# STC8G1K08A.net
KiCad netlist of a schematic drawn in EasyEDA Pro
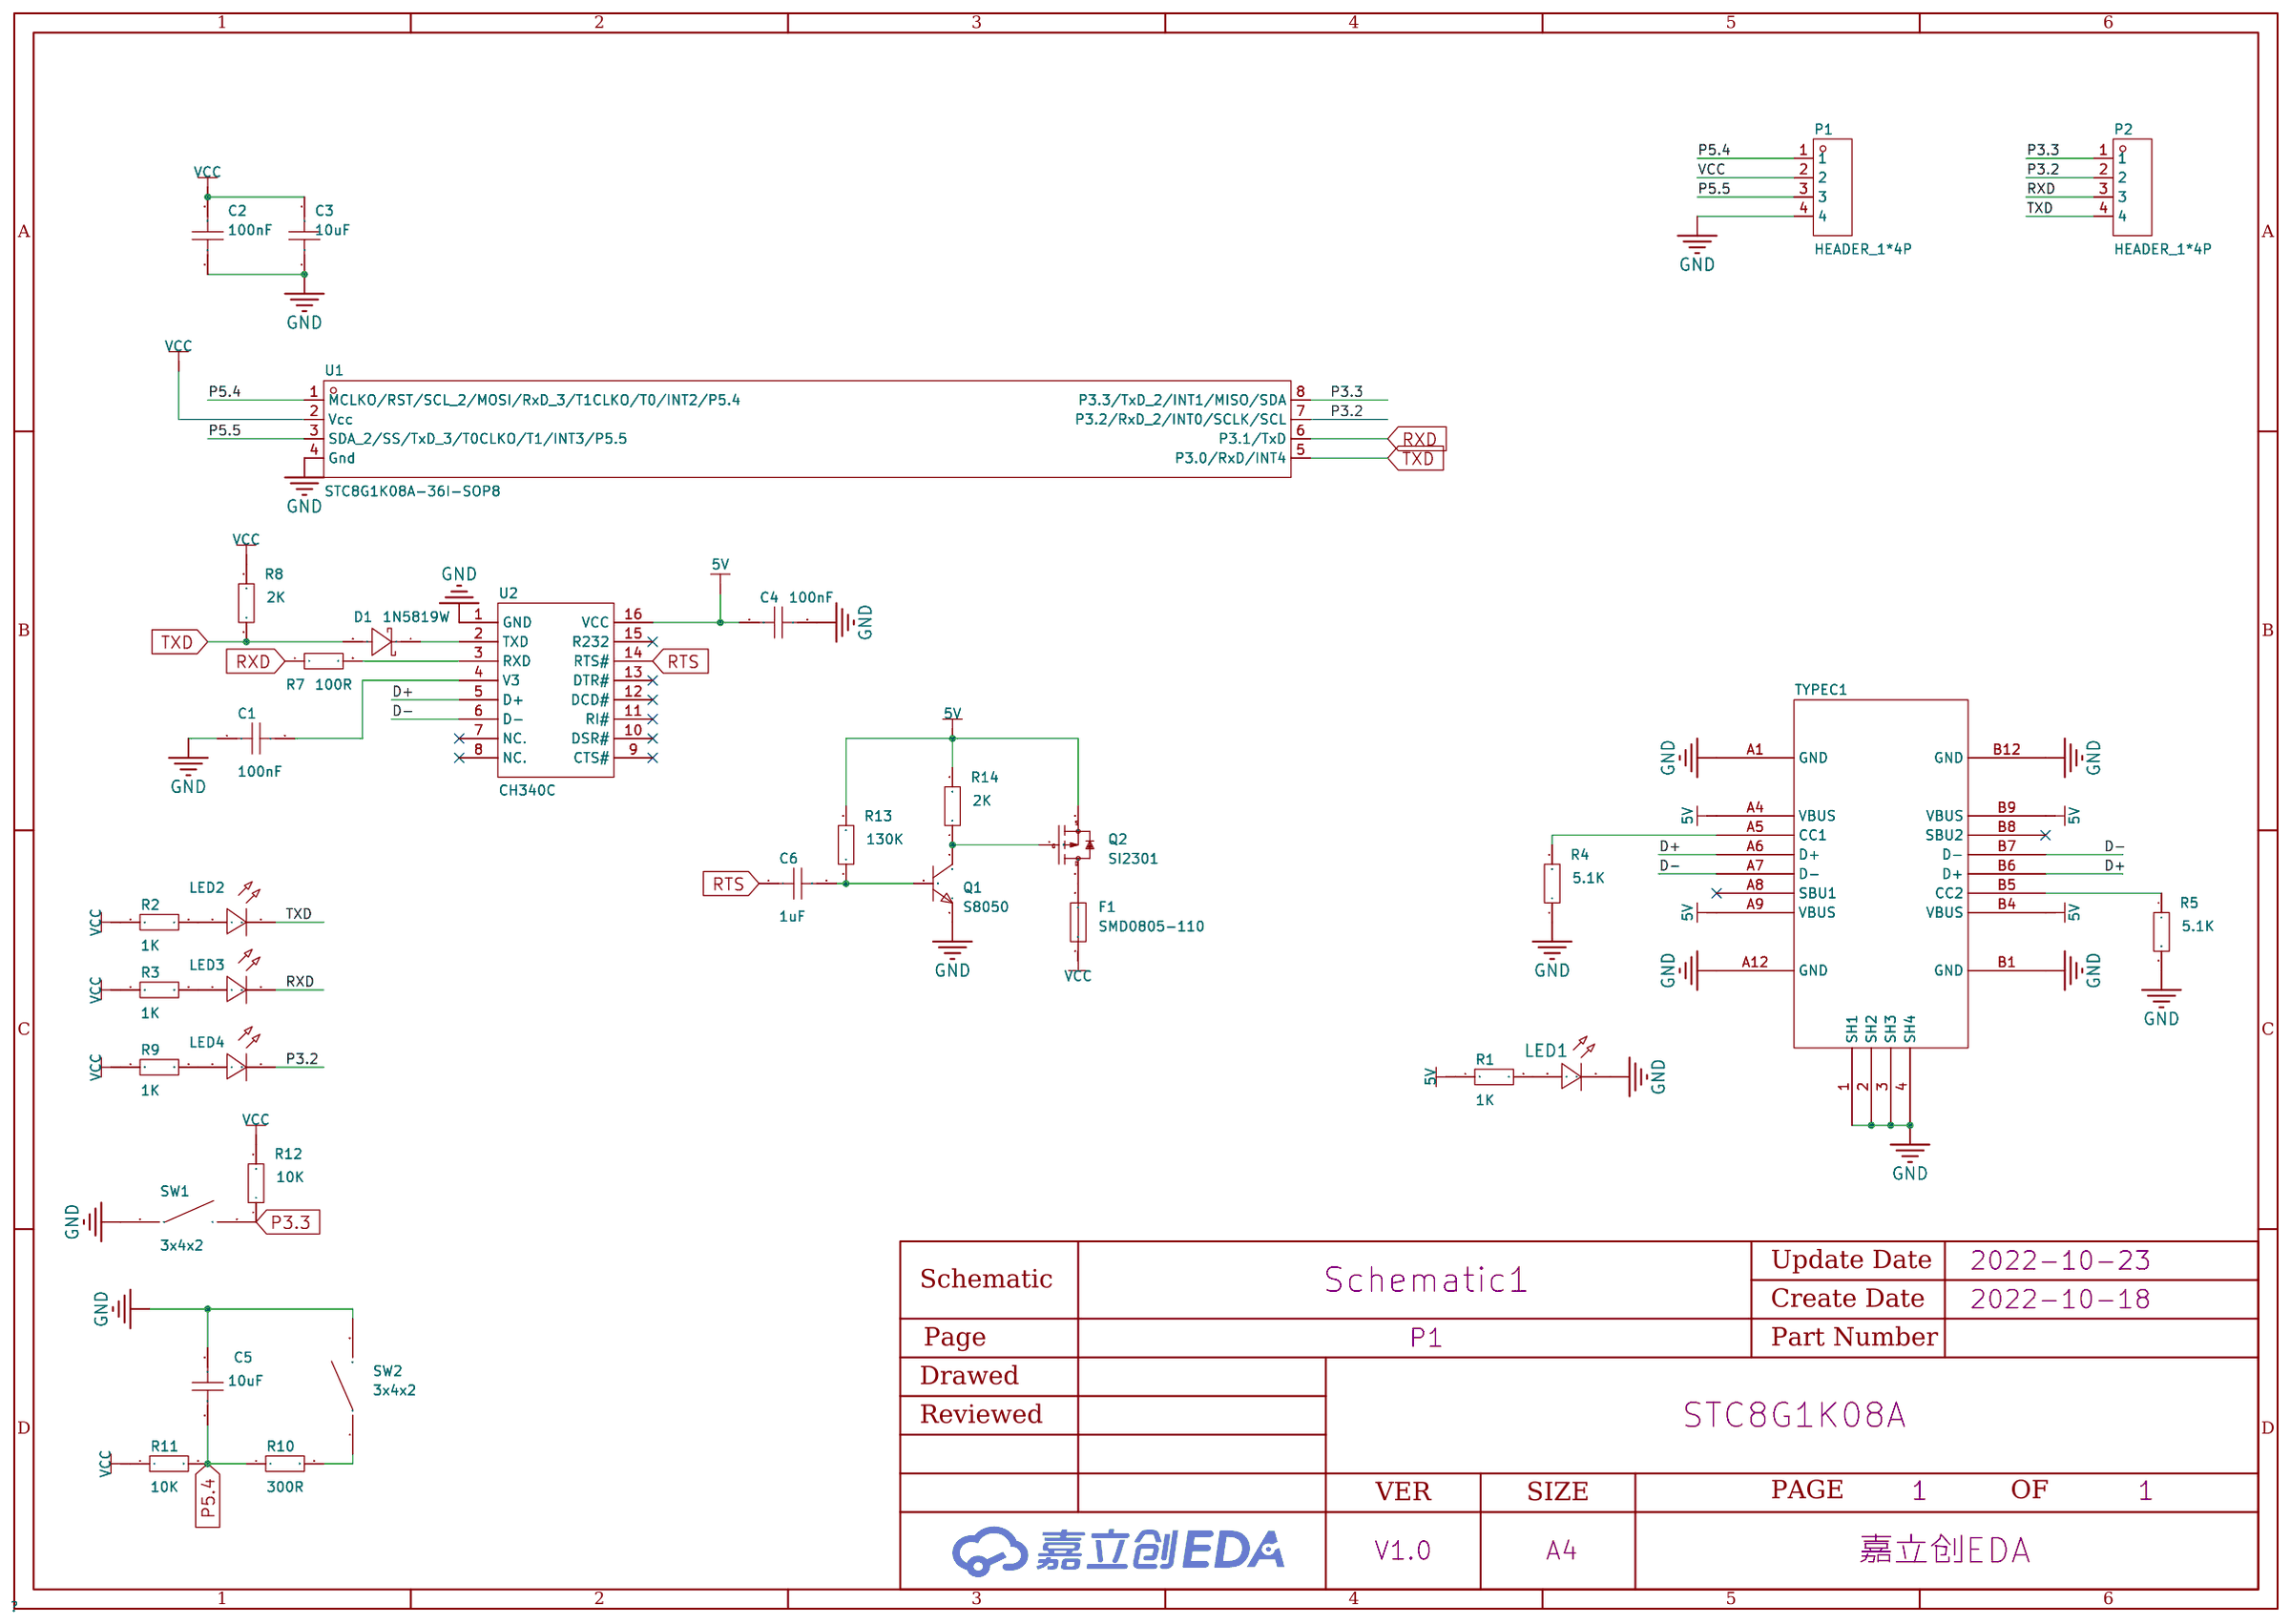
[diagram p0: schematic sheet]

(export (version "E")
  (design (tool "Eeschema 10.0.6"))
  (components
    (comp (ref "C1")
      (value "100nF")
      (footprint "easyedapro:C0603")
      (libsource (lib "easyedapro") (part "C1210X7R475K630NT"))
    )
    (comp (ref "C2")
      (value "100nF")
      (footprint "easyedapro:C0603")
      (libsource (lib "easyedapro") (part "C1210X7R475K630NT"))
    )
    (comp (ref "C3")
      (value "100nF")
      (footprint "easyedapro:C0603")
      (libsource (lib "easyedapro") (part "C1210X7R475K630NT"))
    )
    (comp (ref "C4")
      (value "100nF")
      (footprint "easyedapro:C0603")
      (libsource (lib "easyedapro") (part "C1210X7R475K630NT"))
    )
    (comp (ref "C5")
      (value "100nF")
      (footprint "easyedapro:C0603")
      (libsource (lib "easyedapro") (part "C1210X7R475K630NT"))
    )
    (comp (ref "C6")
      (value "100nF")
      (footprint "easyedapro:C0603")
      (libsource (lib "easyedapro") (part "C1210X7R475K630NT"))
    )
    (comp (ref "D1")
      (value "1N5819W")
      (footprint "easyedapro:SOD-323_L1.7-W1.3-LS2.6-RD-1")
      (description "二极管配置:-;直流反向耐压(Vr):40V;平均整流电流(Io):350mA;正向压降(Vf):600mV@200mA;反向电流(Ir):5A@30V;")
      (fields (field (name "Manufacturer Part") "1N5819WS S4") (field (name "Manufacturer") "KUU"))
      (libsource (lib "easyedapro") (part "1N5819WS S4_C2939001"))
    )
    (comp (ref "F1")
      (value "SMD0805-110")
      (footprint "easyedapro:F0805")
      (fields (field (name "Manufacturer") "DOWO(东沃)"))
      (libsource (lib "easyedapro") (part "SMD0805-110_C883453"))
    )
    (comp (ref "LED1")
      (value "~")
      (footprint "easyedapro:LED0805-RD_RED")
      (libsource (lib "easyedapro") (part "LED_R"))
    )
    (comp (ref "LED2")
      (value "~")
      (footprint "easyedapro:LED0805-RD_RED")
      (libsource (lib "easyedapro") (part "LED_G"))
    )
    (comp (ref "LED3")
      (value "~")
      (footprint "easyedapro:LED0805-RD_RED")
      (libsource (lib "easyedapro") (part "LED_B"))
    )
    (comp (ref "LED4")
      (value "~")
      (footprint "easyedapro:LED0805-RD_RED")
      (libsource (lib "easyedapro") (part "LED_B"))
    )
    (comp (ref "P1")
      (value "HEADER_1*4P")
      (footprint "easyedapro:HDR-TH_4P-P2.54-V-M-1")
      (libsource (lib "easyedapro") (part "HEADER_1*4P"))
    )
    (comp (ref "P2")
      (value "HEADER_1*4P")
      (footprint "easyedapro:HDR-TH_4P-P2.54-V-M-1")
      (libsource (lib "easyedapro") (part "HEADER_1*4P"))
    )
    (comp (ref "Q1")
      (value "S8050")
      (footprint "easyedapro:SOT-23-3_L2.9-W1.3-P1.90-LS2.4-BR")
      (description "NPN 25V 500mA 120-400 SOT-23")
      (fields (field (name "Manufacturer") "Doeshare(德芯)"))
      (libsource (lib "easyedapro") (part "S8050_C2931719"))
    )
    (comp (ref "Q2")
      (value "SI2301")
      (footprint "easyedapro:SOT-23-3_L2.9-W1.6-P1.90-LS2.8-BR")
      (fields (field (name "Manufacturer") "KUU"))
      (libsource (lib "easyedapro") (part "SI2301_C2985938"))
    )
    (comp (ref "R1") (value "10K") (footprint "easyedapro:R0603") (libsource (lib "easyedapro") (part "电阻")))
    (comp (ref "R2") (value "10K") (footprint "easyedapro:R0603") (libsource (lib "easyedapro") (part "电阻")))
    (comp (ref "R3") (value "10K") (footprint "easyedapro:R0603") (libsource (lib "easyedapro") (part "电阻")))
    (comp (ref "R4") (value "10K") (footprint "easyedapro:R0603") (libsource (lib "easyedapro") (part "电阻")))
    (comp (ref "R5") (value "10K") (footprint "easyedapro:R0603") (libsource (lib "easyedapro") (part "电阻")))
    (comp (ref "R7") (value "10K") (footprint "easyedapro:R0603") (libsource (lib "easyedapro") (part "电阻")))
    (comp (ref "R8") (value "10K") (footprint "easyedapro:R0603") (libsource (lib "easyedapro") (part "电阻")))
    (comp (ref "R9") (value "10K") (footprint "easyedapro:R0603") (libsource (lib "easyedapro") (part "电阻")))
    (comp (ref "R10") (value "10K") (footprint "easyedapro:R0603") (libsource (lib "easyedapro") (part "电阻")))
    (comp (ref "R11") (value "10K") (footprint "easyedapro:R0603") (libsource (lib "easyedapro") (part "电阻")))
    (comp (ref "R12") (value "10K") (footprint "easyedapro:R0603") (libsource (lib "easyedapro") (part "电阻")))
    (comp (ref "R13") (value "10K") (footprint "easyedapro:R0603") (libsource (lib "easyedapro") (part "电阻")))
    (comp (ref "R14") (value "10K") (footprint "easyedapro:R0603") (libsource (lib "easyedapro") (part "电阻")))
    (comp (ref "SW1")
      (value "3x4x2")
      (footprint "easyedapro:SW-SMD_L4.0-W2.9-LS5.0")
      (fields
        (field (name "Manufacturer Part") "TS-1185-C-A-B-B")
        (field (name "Manufacturer") "XKB Connectivity(中国星坤)")
      )
      (libsource (lib "easyedapro") (part "TS-1185-C-A-B-B"))
    )
    (comp (ref "SW2")
      (value "3x4x2")
      (footprint "easyedapro:SW-SMD_L4.0-W2.9-LS5.0")
      (fields
        (field (name "Manufacturer Part") "TS-1185-C-A-B-B")
        (field (name "Manufacturer") "XKB Connectivity(中国星坤)")
      )
      (libsource (lib "easyedapro") (part "TS-1185-C-A-B-B"))
    )
    (comp (ref "TYPEC1")
      (value "~")
      (footprint "easyedapro:TypeC-16p")
      (libsource (lib "easyedapro") (part "Type C"))
    )
    (comp (ref "U1")
      (value "STC8G1K08A-36I-SOP8")
      (footprint "easyedapro:SOP-8_L5.0-W4.0-P1.27-LS6.0-BL")
      (fields (field (name "Manufacturer") "STC(宏晶)"))
      (libsource (lib "easyedapro") (part "STC8G1K08A-36I-SOP8"))
    )
    (comp (ref "U2")
      (value "CH340C")
      (footprint "easyedapro:SOP-16_L10.0-W3.9-P1.27-LS6.0-BL")
      (description "类型:Transceiver;协议类别:USB 2.0;驱动器/接收器数:-;数据速率:2Mbps;")
      (fields (field (name "Manufacturer") "WCH(南京沁恒)"))
      (libsource (lib "easyedapro") (part "CH340C"))
    )
  )
  (nets
    (net (code "1") (name "/D+") (class "Default")
      (node (ref "TYPEC1") (pin "A6") (pinfunction "D+_A6") (pintype "input"))
      (node (ref "TYPEC1") (pin "B6") (pinfunction "D+_B6") (pintype "input"))
      (node (ref "U2") (pin "5") (pinfunction "D+_5") (pintype "input"))
    )
    (net (code "2") (name "/D-") (class "Default")
      (node (ref "TYPEC1") (pin "A7") (pinfunction "D-_A7") (pintype "input"))
      (node (ref "TYPEC1") (pin "B7") (pinfunction "D-_B7") (pintype "input"))
      (node (ref "U2") (pin "6") (pinfunction "D-_6") (pintype "input"))
    )
    (net (code "3") (name "/P3.2") (class "Default")
      (node (ref "LED4") (pin "1") (pinfunction "C_1") (pintype "input"))
      (node (ref "P2") (pin "2") (pinfunction "2_2") (pintype "input"))
      (node (ref "U1") (pin "7") (pinfunction "P3.2/RxD_2/INT0/SCLK/SCL_7") (pintype "input"))
    )
    (net (code "4") (name "/P5.5") (class "Default")
      (node (ref "P1") (pin "3") (pinfunction "3_3") (pintype "input"))
      (node (ref "U1") (pin "3") (pinfunction "SDA_2/SS/TxD_3/T0CLKO/T1/INT3/P5.5_3") (pintype "input"))
    )
    (net (code "5") (name "5V") (class "Default")
      (node (ref "C4") (pin "2") (pinfunction "2_2") (pintype "input"))
      (node (ref "Q2") (pin "2") (pinfunction "S_2") (pintype "input"))
      (node (ref "R1") (pin "1") (pinfunction "1_1") (pintype "input"))
      (node (ref "R13") (pin "2") (pinfunction "2_2") (pintype "input"))
      (node (ref "R14") (pin "2") (pinfunction "2_2") (pintype "input"))
      (node (ref "TYPEC1") (pin "A4") (pinfunction "VBUS_A4") (pintype "input"))
      (node (ref "TYPEC1") (pin "A9") (pinfunction "VBUS_A9") (pintype "input"))
      (node (ref "TYPEC1") (pin "B4") (pinfunction "VBUS_B4") (pintype "input"))
      (node (ref "TYPEC1") (pin "B9") (pinfunction "VBUS_B9") (pintype "input"))
      (node (ref "U2") (pin "16") (pinfunction "VCC_16") (pintype "input"))
    )
    (net (code "6") (name "GND") (class "Default")
      (node (ref "C1") (pin "1") (pinfunction "1_1") (pintype "input"))
      (node (ref "C2") (pin "1") (pinfunction "1_1") (pintype "input"))
      (node (ref "C3") (pin "1") (pinfunction "1_1") (pintype "input"))
      (node (ref "C4") (pin "1") (pinfunction "1_1") (pintype "input"))
      (node (ref "C5") (pin "2") (pinfunction "2_2") (pintype "input"))
      (node (ref "LED1") (pin "1") (pinfunction "C_1") (pintype "input"))
      (node (ref "P1") (pin "4") (pinfunction "4_4") (pintype "input"))
      (node (ref "Q1") (pin "2") (pinfunction "E_2") (pintype "input"))
      (node (ref "R4") (pin "1") (pinfunction "1_1") (pintype "input"))
      (node (ref "R5") (pin "2") (pinfunction "2_2") (pintype "input"))
      (node (ref "SW1") (pin "1") (pinfunction "1_1") (pintype "input"))
      (node (ref "SW2") (pin "2") (pinfunction "2_2") (pintype "input"))
      (node (ref "TYPEC1") (pin "1") (pinfunction "SH1_1") (pintype "input"))
      (node (ref "TYPEC1") (pin "2") (pinfunction "SH2_2") (pintype "input"))
      (node (ref "TYPEC1") (pin "3") (pinfunction "SH3_3") (pintype "input"))
      (node (ref "TYPEC1") (pin "4") (pinfunction "SH4_4") (pintype "input"))
      (node (ref "TYPEC1") (pin "A1") (pinfunction "GND_A1") (pintype "input"))
      (node (ref "TYPEC1") (pin "A12") (pinfunction "GND_A12") (pintype "input"))
      (node (ref "TYPEC1") (pin "B1") (pinfunction "GND_B1") (pintype "input"))
      (node (ref "TYPEC1") (pin "B12") (pinfunction "GND_B12") (pintype "input"))
      (node (ref "U1") (pin "4") (pinfunction "Gnd_4") (pintype "input"))
      (node (ref "U2") (pin "1") (pinfunction "GND_1") (pintype "input"))
    )
    (net (code "7") (name "Net-(D1-K)") (class "Default")
      (node (ref "D1") (pin "1") (pinfunction "K_1") (pintype "input"))
      (node (ref "U2") (pin "2") (pinfunction "TXD_2") (pintype "input"))
    )
    (net (code "8") (name "Net-(LED1-A)") (class "Default")
      (node (ref "LED1") (pin "2") (pinfunction "A_2") (pintype "input"))
      (node (ref "R1") (pin "2") (pinfunction "2_2") (pintype "input"))
    )
    (net (code "9") (name "Net-(LED2-A)") (class "Default")
      (node (ref "LED2") (pin "2") (pinfunction "A_2") (pintype "input"))
      (node (ref "R2") (pin "2") (pinfunction "2_2") (pintype "input"))
    )
    (net (code "10") (name "Net-(LED3-A)") (class "Default")
      (node (ref "LED3") (pin "2") (pinfunction "A_2") (pintype "input"))
      (node (ref "R3") (pin "2") (pinfunction "2_2") (pintype "input"))
    )
    (net (code "11") (name "Net-(LED4-A)") (class "Default")
      (node (ref "LED4") (pin "2") (pinfunction "A_2") (pintype "input"))
      (node (ref "R9") (pin "2") (pinfunction "2_2") (pintype "input"))
    )
    (net (code "12") (name "Net-(Q1-B)") (class "Default")
      (node (ref "C6") (pin "2") (pinfunction "2_2") (pintype "input"))
      (node (ref "Q1") (pin "1") (pinfunction "B_1") (pintype "input"))
      (node (ref "R13") (pin "1") (pinfunction "1_1") (pintype "input"))
    )
    (net (code "13") (name "Net-(Q1-C)") (class "Default")
      (node (ref "Q1") (pin "3") (pinfunction "C_3") (pintype "input"))
      (node (ref "Q2") (pin "1") (pinfunction "G_1") (pintype "input"))
      (node (ref "R14") (pin "1") (pinfunction "1_1") (pintype "input"))
    )
    (net (code "14") (name "Net-(Q2-D)") (class "Default")
      (node (ref "F1") (pin "2") (pinfunction "2_2") (pintype "input"))
      (node (ref "Q2") (pin "3") (pinfunction "D_3") (pintype "input"))
    )
    (net (code "15") (name "Net-(R10-Pad2)") (class "Default")
      (node (ref "R10") (pin "2") (pinfunction "2_2") (pintype "input"))
      (node (ref "SW2") (pin "1") (pinfunction "1_1") (pintype "input"))
    )
    (net (code "16") (name "Net-(TYPEC1-CC1)") (class "Default")
      (node (ref "R4") (pin "2") (pinfunction "2_2") (pintype "input"))
      (node (ref "TYPEC1") (pin "A5") (pinfunction "CC1_A5") (pintype "input"))
    )
    (net (code "17") (name "Net-(TYPEC1-CC2)") (class "Default")
      (node (ref "R5") (pin "1") (pinfunction "1_1") (pintype "input"))
      (node (ref "TYPEC1") (pin "B5") (pinfunction "CC2_B5") (pintype "input"))
    )
    (net (code "18") (name "Net-(U2-RXD)") (class "Default")
      (node (ref "R7") (pin "2") (pinfunction "2_2") (pintype "input"))
      (node (ref "U2") (pin "3") (pinfunction "RXD_3") (pintype "input"))
    )
    (net (code "19") (name "Net-(U2-V3)") (class "Default")
      (node (ref "C1") (pin "2") (pinfunction "2_2") (pintype "input"))
      (node (ref "U2") (pin "4") (pinfunction "V3_4") (pintype "input"))
    )
    (net (code "20") (name "P3.3") (class "Default")
      (node (ref "P2") (pin "1") (pinfunction "1_1") (pintype "input"))
      (node (ref "R12") (pin "1") (pinfunction "1_1") (pintype "input"))
      (node (ref "SW1") (pin "2") (pinfunction "2_2") (pintype "input"))
      (node (ref "U1") (pin "8") (pinfunction "P3.3/TxD_2/INT1/MISO/SDA_8") (pintype "input"))
    )
    (net (code "21") (name "P5.4") (class "Default")
      (node (ref "C5") (pin "1") (pinfunction "1_1") (pintype "input"))
      (node (ref "P1") (pin "1") (pinfunction "1_1") (pintype "input"))
      (node (ref "R10") (pin "1") (pinfunction "1_1") (pintype "input"))
      (node (ref "R11") (pin "2") (pinfunction "2_2") (pintype "input"))
      (node (ref "U1") (pin "1") (pinfunction "MCLKO/RST/SCL_2/MOSI/RxD_3/T1CLKO/T0/INT2/P5.4_1") (pintype "input"))
    )
    (net (code "22") (name "RTS") (class "Default")
      (node (ref "C6") (pin "1") (pinfunction "1_1") (pintype "input"))
      (node (ref "U2") (pin "14") (pinfunction "RTS#_14") (pintype "input"))
    )
    (net (code "23") (name "RXD") (class "Default")
      (node (ref "LED3") (pin "1") (pinfunction "C_1") (pintype "input"))
      (node (ref "P2") (pin "3") (pinfunction "3_3") (pintype "input"))
      (node (ref "R7") (pin "1") (pinfunction "1_1") (pintype "input"))
      (node (ref "U1") (pin "6") (pinfunction "P3.1/TxD_6") (pintype "input"))
    )
    (net (code "24") (name "TXD") (class "Default")
      (node (ref "D1") (pin "2") (pinfunction "A_2") (pintype "input"))
      (node (ref "LED2") (pin "1") (pinfunction "C_1") (pintype "input"))
      (node (ref "P2") (pin "4") (pinfunction "4_4") (pintype "input"))
      (node (ref "R8") (pin "1") (pinfunction "1_1") (pintype "input"))
      (node (ref "U1") (pin "5") (pinfunction "P3.0/RxD/INT4_5") (pintype "input"))
    )
    (net (code "25") (name "VCC") (class "Default")
      (node (ref "C2") (pin "2") (pinfunction "2_2") (pintype "input"))
      (node (ref "C3") (pin "2") (pinfunction "2_2") (pintype "input"))
      (node (ref "F1") (pin "1") (pinfunction "1_1") (pintype "input"))
      (node (ref "P1") (pin "2") (pinfunction "2_2") (pintype "input"))
      (node (ref "R11") (pin "1") (pinfunction "1_1") (pintype "input"))
      (node (ref "R12") (pin "2") (pinfunction "2_2") (pintype "input"))
      (node (ref "R2") (pin "1") (pinfunction "1_1") (pintype "input"))
      (node (ref "R3") (pin "1") (pinfunction "1_1") (pintype "input"))
      (node (ref "R8") (pin "2") (pinfunction "2_2") (pintype "input"))
      (node (ref "R9") (pin "1") (pinfunction "1_1") (pintype "input"))
      (node (ref "U1") (pin "2") (pinfunction "Vcc_2") (pintype "input"))
    )
    (net (code "26") (name "unconnected-(TYPEC1-SBU1-PadA8)") (class "Default")
      (node (ref "TYPEC1") (pin "A8") (pinfunction "SBU1_A8") (pintype "input+no_connect"))
    )
    (net (code "27") (name "unconnected-(TYPEC1-SBU2-PadB8)") (class "Default")
      (node (ref "TYPEC1") (pin "B8") (pinfunction "SBU2_B8") (pintype "input+no_connect"))
    )
    (net (code "28") (name "unconnected-(U2-CTS#-Pad9)") (class "Default")
      (node (ref "U2") (pin "9") (pinfunction "CTS#_9") (pintype "input+no_connect"))
    )
    (net (code "29") (name "unconnected-(U2-DCD#-Pad12)") (class "Default")
      (node (ref "U2") (pin "12") (pinfunction "DCD#_12") (pintype "input+no_connect"))
    )
    (net (code "30") (name "unconnected-(U2-DSR#-Pad10)") (class "Default")
      (node (ref "U2") (pin "10") (pinfunction "DSR#_10") (pintype "input+no_connect"))
    )
    (net (code "31") (name "unconnected-(U2-DTR#-Pad13)") (class "Default")
      (node (ref "U2") (pin "13") (pinfunction "DTR#_13") (pintype "input+no_connect"))
    )
    (net (code "32") (name "unconnected-(U2-NC.-Pad7)") (class "Default")
      (node (ref "U2") (pin "7") (pinfunction "NC._7") (pintype "input+no_connect"))
    )
    (net (code "33") (name "unconnected-(U2-NC.-Pad8)") (class "Default")
      (node (ref "U2") (pin "8") (pinfunction "NC._8") (pintype "input+no_connect"))
    )
    (net (code "34") (name "unconnected-(U2-R232-Pad15)") (class "Default")
      (node (ref "U2") (pin "15") (pinfunction "R232_15") (pintype "input+no_connect"))
    )
    (net (code "35") (name "unconnected-(U2-RI#-Pad11)") (class "Default")
      (node (ref "U2") (pin "11") (pinfunction "RI#_11") (pintype "input+no_connect"))
    )
  )
)
